# shoot1.net
KiCad netlist of a schematic drawn in Altium Designer
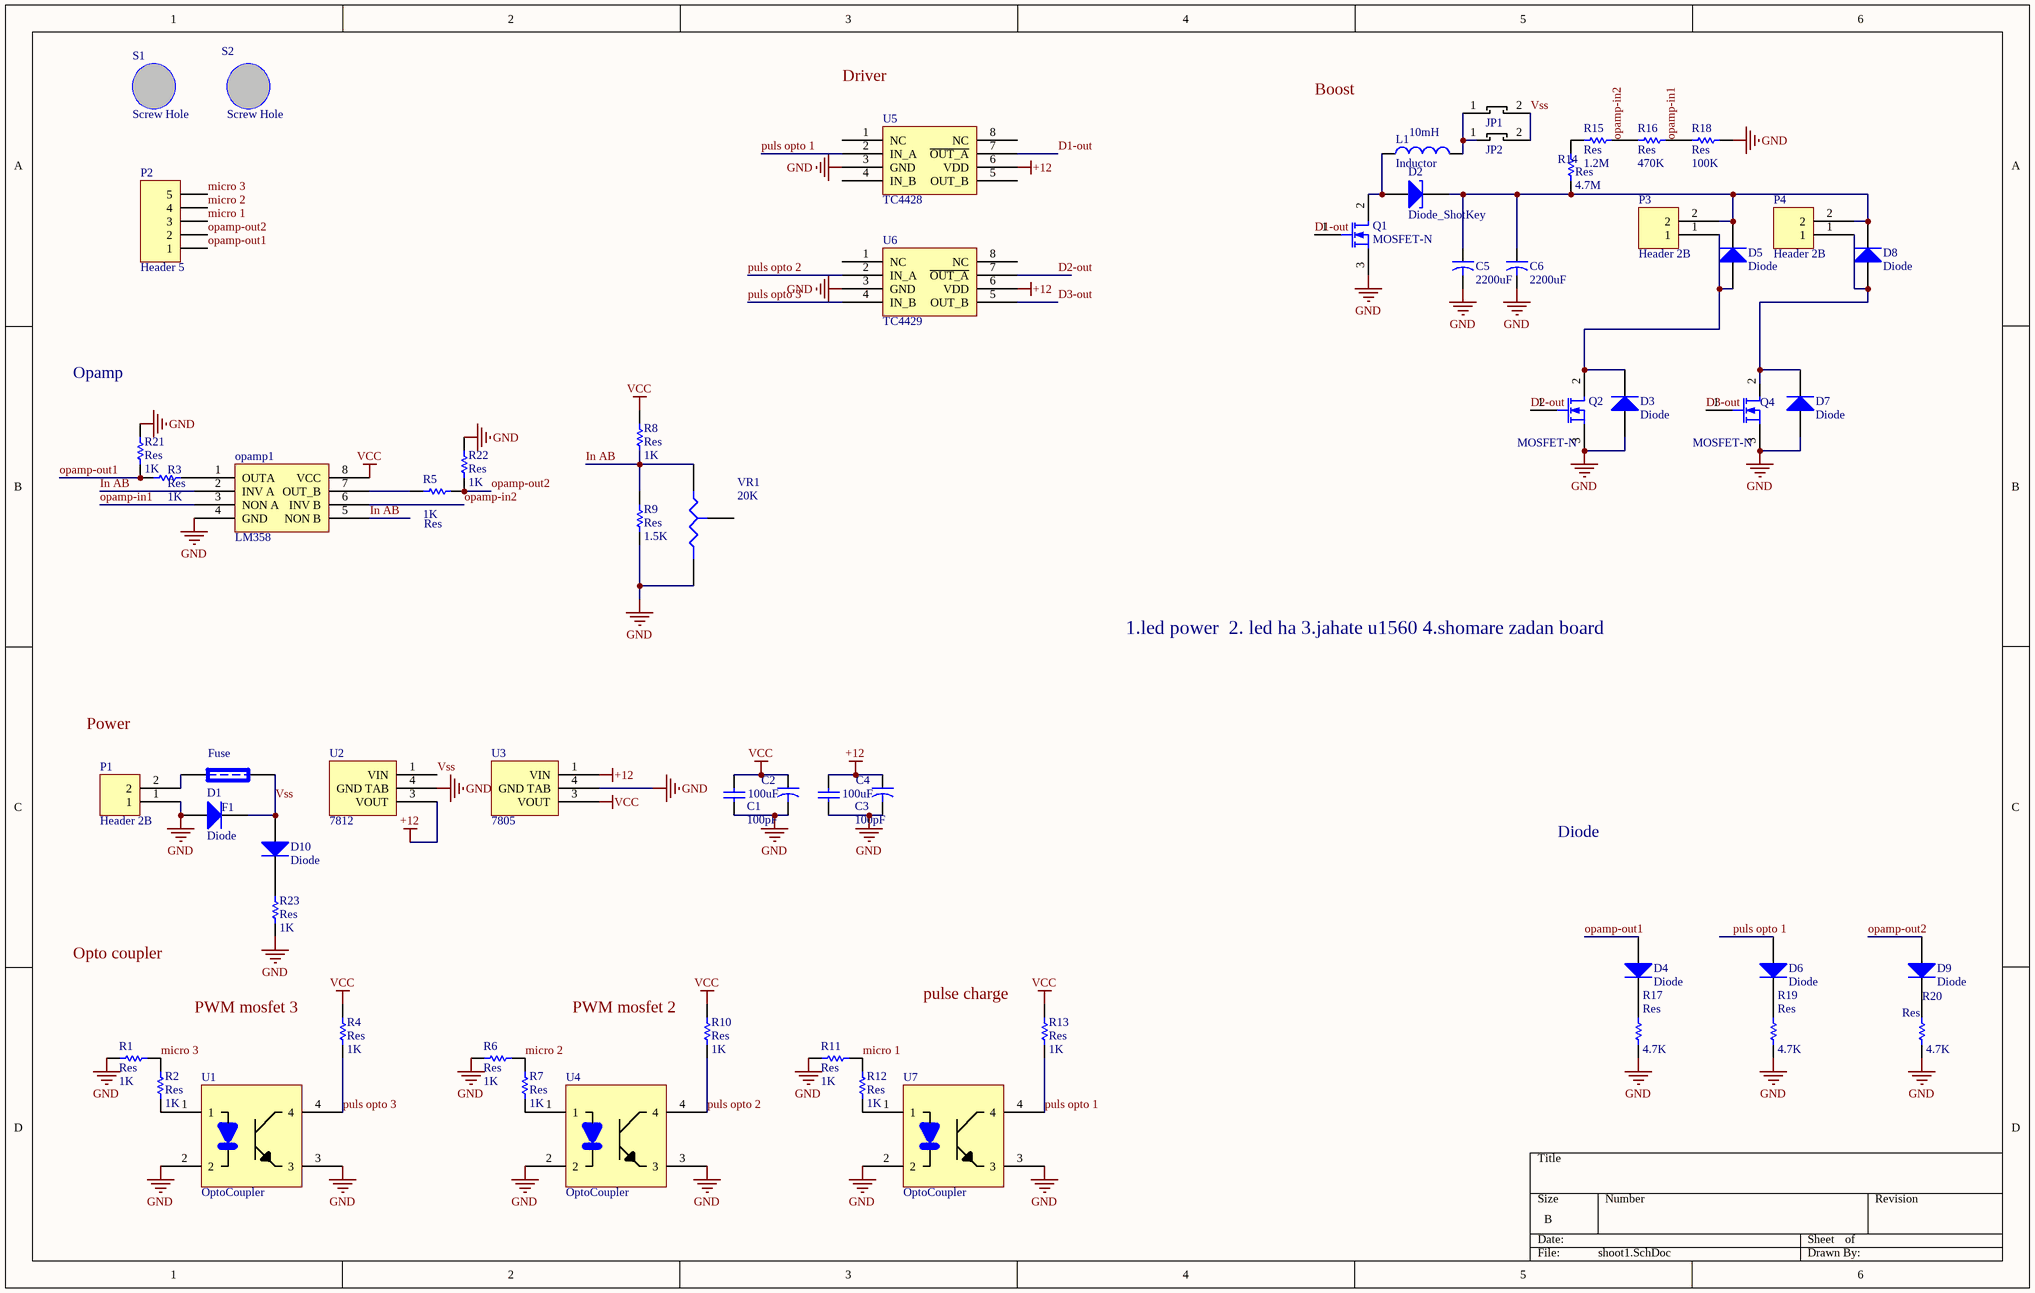
[diagram p0: shoot1.SchDoc]

(export (version "E")
  (design (tool "Eeschema 10.0.6"))
  (components
    (comp (ref "C1")
      (value "100pF")
      (footprint "2012[0805]")
      (description "Capacitor")
      (fields (field (name "Comment") "Cap_UP") (field (name "PUBLISHER") "Altium Limited"))
      (libsource (lib "KN2CLib") (part "Cap_UP"))
    )
    (comp (ref "C2")
      (value "100uF")
      (footprint "EL_M")
      (description "Capacitor")
      (fields (field (name "Comment") "Cap_El") (field (name "PUBLISHER") "Altium Limited"))
      (libsource (lib "KN2CLib") (part "Cap_El"))
    )
    (comp (ref "C3")
      (value "100pF")
      (footprint "2012[0805]")
      (description "Capacitor")
      (fields (field (name "Comment") "Cap_UP") (field (name "PUBLISHER") "Altium Limited"))
      (libsource (lib "KN2CLib") (part "Cap_UP"))
    )
    (comp (ref "C4")
      (value "100uF")
      (footprint "EL_M")
      (description "Capacitor")
      (fields (field (name "Comment") "Cap_El") (field (name "PUBLISHER") "Altium Limited"))
      (libsource (lib "KN2CLib") (part "Cap_El"))
    )
    (comp (ref "C5")
      (value "2200uF")
      (footprint "CAP")
      (description "Capacitor")
      (fields (field (name "Comment") "Cap_El_200V") (field (name "PUBLISHER") "Altium Limited"))
      (libsource (lib "KN2CLib") (part "Cap_El_200V"))
    )
    (comp (ref "C6")
      (value "2200uF")
      (footprint "CAP")
      (description "Capacitor")
      (fields (field (name "Comment") "Cap_El_200V") (field (name "PUBLISHER") "Altium Limited"))
      (libsource (lib "KN2CLib") (part "Cap_El_200V"))
    )
    (comp (ref "D1")
      (value "Diode")
      (footprint "US1M")
      (description "1 Amp General Purpose Rectifier")
      (fields (field (name "PUBLISHER") "Altium Limited"))
      (libsource (lib "KN2CLib") (part "Diode"))
    )
    (comp (ref "D2")
      (value "Diode_ShotKey")
      (footprint "TO-220A - duplicate")
      (description "1 Amp General Purpose Rectifier")
      (fields (field (name "PUBLISHER") "Altium Limited"))
      (libsource (lib "KN2CLib") (part "Diode_ShotKey"))
    )
    (comp (ref "D3")
      (value "Diode")
      (footprint "DIO10.46-5.3X2.8")
      (description "1 Amp General Purpose Rectifier")
      (fields (field (name "PUBLISHER") "Altium Limited"))
      (libsource (lib "KN2CLib") (part "Diode"))
    )
    (comp (ref "D4")
      (value "Diode")
      (footprint "2012[0805]")
      (description "1 Amp General Purpose Rectifier")
      (fields (field (name "PUBLISHER") "Altium Limited"))
      (libsource (lib "KN2CLib") (part "Diode"))
    )
    (comp (ref "D5")
      (value "Diode")
      (footprint "DIO10.46-5.3X2.8")
      (description "1 Amp General Purpose Rectifier")
      (fields (field (name "PUBLISHER") "Altium Limited"))
      (libsource (lib "KN2CLib") (part "Diode"))
    )
    (comp (ref "D6")
      (value "Diode")
      (footprint "2012[0805]")
      (description "1 Amp General Purpose Rectifier")
      (fields (field (name "PUBLISHER") "Altium Limited"))
      (libsource (lib "KN2CLib") (part "Diode"))
    )
    (comp (ref "D7")
      (value "Diode")
      (footprint "DIO10.46-5.3X2.8")
      (description "1 Amp General Purpose Rectifier")
      (fields (field (name "PUBLISHER") "Altium Limited"))
      (libsource (lib "KN2CLib") (part "Diode"))
    )
    (comp (ref "D8")
      (value "Diode")
      (footprint "DIO10.46-5.3X2.8")
      (description "1 Amp General Purpose Rectifier")
      (fields (field (name "PUBLISHER") "Altium Limited"))
      (libsource (lib "KN2CLib") (part "Diode"))
    )
    (comp (ref "D9")
      (value "Diode")
      (footprint "2012[0805]")
      (description "1 Amp General Purpose Rectifier")
      (fields (field (name "PUBLISHER") "Altium Limited"))
      (libsource (lib "KN2CLib") (part "Diode"))
    )
    (comp (ref "D10")
      (value "Diode")
      (footprint "2012[0805]")
      (description "1 Amp General Purpose Rectifier")
      (fields (field (name "PUBLISHER") "Altium Limited"))
      (libsource (lib "KN2CLib") (part "Diode"))
    )
    (comp (ref "F1")
      (value "Fuse")
      (footprint "fuse new")
      (fields (field (name "PUBLISHER") "Altium Limited"))
      (libsource (lib "KN2CLib") (part "Fuse"))
    )
    (comp (ref "JP1") (value "JUMPER") (footprint "JPR") (libsource (lib "KN2CLib") (part "JUMPER")))
    (comp (ref "JP2") (value "JUMPER") (footprint "JPR") (libsource (lib "KN2CLib") (part "JUMPER")))
    (comp (ref "L1")
      (value "Inductor")
      (footprint "Mh2")
      (fields (field (name "ALTIUM_VALUE") "10mH") (field (name "PUBLISHER") "Altium Limited"))
      (libsource (lib "KN2CLib") (part "Inductor"))
    )
    (comp (ref "opamp1")
      (value "LM358")
      (footprint "8 pin SOIC_N")
      (description "Dual MOSFET Driver")
      (libsource (lib "KN2CLib") (part "7667"))
    )
    (comp (ref "P1") (value "Header 2B") (footprint "BHDR1X2") (libsource (lib "KN2CLib") (part "Header 2B")))
    (comp (ref "P2")
      (value "Header 5")
      (footprint "SHEADER 5")
      (description "Header, 5-Pin")
      (fields (field (name "PUBLISHER") "Altium Limited"))
      (libsource (lib "KN2CLib") (part "Header 5"))
    )
    (comp (ref "P3") (value "Header 2B") (footprint "BHDR1X2") (libsource (lib "KN2CLib") (part "Header 2B")))
    (comp (ref "P4") (value "Header 2B") (footprint "BHDR1X2") (libsource (lib "KN2CLib") (part "Header 2B")))
    (comp (ref "Q1")
      (value "MOSFET-N")
      (footprint "TO247")
      (description "N-Channel MOSFET")
      (fields (field (name "PUBLISHER") "Altium Limited"))
      (libsource (lib "KN2CLib") (part "MOSFET-N"))
    )
    (comp (ref "Q2")
      (value "MOSFET-N")
      (footprint "TO247")
      (description "N-Channel MOSFET")
      (fields (field (name "PUBLISHER") "Altium Limited"))
      (libsource (lib "KN2CLib") (part "MOSFET-N"))
    )
    (comp (ref "Q4")
      (value "MOSFET-N")
      (footprint "TO247")
      (description "N-Channel MOSFET")
      (fields (field (name "PUBLISHER") "Altium Limited"))
      (libsource (lib "KN2CLib") (part "MOSFET-N"))
    )
    (comp (ref "R1")
      (value "Res")
      (footprint "2012[0805]")
      (description "Semiconductor Resistor")
      (fields (field (name "ALTIUM_VALUE") "1K") (field (name "PUBLISHER") "Altium Limited"))
      (libsource (lib "KN2CLib") (part "Res"))
    )
    (comp (ref "R2")
      (value "Res")
      (footprint "2012[0805]")
      (description "Semiconductor Resistor")
      (fields (field (name "ALTIUM_VALUE") "1K") (field (name "PUBLISHER") "Altium Limited"))
      (libsource (lib "KN2CLib") (part "Res"))
    )
    (comp (ref "R3")
      (value "Res")
      (footprint "2012[0805]")
      (description "Semiconductor Resistor")
      (fields (field (name "ALTIUM_VALUE") "1K") (field (name "PUBLISHER") "Altium Limited"))
      (libsource (lib "KN2CLib") (part "Res"))
    )
    (comp (ref "R4")
      (value "Res")
      (footprint "2012[0805]")
      (description "Semiconductor Resistor")
      (fields (field (name "ALTIUM_VALUE") "1K") (field (name "PUBLISHER") "Altium Limited"))
      (libsource (lib "KN2CLib") (part "Res"))
    )
    (comp (ref "R5")
      (value "Res")
      (footprint "2012[0805]")
      (description "Semiconductor Resistor")
      (fields (field (name "ALTIUM_VALUE") "1K") (field (name "PUBLISHER") "Altium Limited"))
      (libsource (lib "KN2CLib") (part "Res"))
    )
    (comp (ref "R6")
      (value "Res")
      (footprint "2012[0805]")
      (description "Semiconductor Resistor")
      (fields (field (name "ALTIUM_VALUE") "1K") (field (name "PUBLISHER") "Altium Limited"))
      (libsource (lib "KN2CLib") (part "Res"))
    )
    (comp (ref "R7")
      (value "Res")
      (footprint "2012[0805]")
      (description "Semiconductor Resistor")
      (fields (field (name "ALTIUM_VALUE") "1K") (field (name "PUBLISHER") "Altium Limited"))
      (libsource (lib "KN2CLib") (part "Res"))
    )
    (comp (ref "R8")
      (value "Res")
      (footprint "2012[0805]")
      (description "Semiconductor Resistor")
      (fields (field (name "ALTIUM_VALUE") "1K") (field (name "PUBLISHER") "Altium Limited"))
      (libsource (lib "KN2CLib") (part "Res"))
    )
    (comp (ref "R9")
      (value "Res")
      (footprint "2012[0805]")
      (description "Semiconductor Resistor")
      (fields (field (name "ALTIUM_VALUE") "1.5K") (field (name "PUBLISHER") "Altium Limited"))
      (libsource (lib "KN2CLib") (part "Res"))
    )
    (comp (ref "R10")
      (value "Res")
      (footprint "2012[0805]")
      (description "Semiconductor Resistor")
      (fields (field (name "ALTIUM_VALUE") "1K") (field (name "PUBLISHER") "Altium Limited"))
      (libsource (lib "KN2CLib") (part "Res"))
    )
    (comp (ref "R11")
      (value "Res")
      (footprint "2012[0805]")
      (description "Semiconductor Resistor")
      (fields (field (name "ALTIUM_VALUE") "1K") (field (name "PUBLISHER") "Altium Limited"))
      (libsource (lib "KN2CLib") (part "Res"))
    )
    (comp (ref "R12")
      (value "Res")
      (footprint "2012[0805]")
      (description "Semiconductor Resistor")
      (fields (field (name "ALTIUM_VALUE") "1K") (field (name "PUBLISHER") "Altium Limited"))
      (libsource (lib "KN2CLib") (part "Res"))
    )
    (comp (ref "R13")
      (value "Res")
      (footprint "2012[0805]")
      (description "Semiconductor Resistor")
      (fields (field (name "ALTIUM_VALUE") "1K") (field (name "PUBLISHER") "Altium Limited"))
      (libsource (lib "KN2CLib") (part "Res"))
    )
    (comp (ref "R14")
      (value "Res")
      (footprint "2012[0805]")
      (description "Semiconductor Resistor")
      (fields (field (name "ALTIUM_VALUE") "4.7M") (field (name "PUBLISHER") "Altium Limited"))
      (libsource (lib "KN2CLib") (part "Res"))
    )
    (comp (ref "R15")
      (value "Res")
      (footprint "2012[0805]")
      (description "Semiconductor Resistor")
      (fields (field (name "ALTIUM_VALUE") "1.2M") (field (name "PUBLISHER") "Altium Limited"))
      (libsource (lib "KN2CLib") (part "Res"))
    )
    (comp (ref "R16")
      (value "Res")
      (footprint "2012[0805]")
      (description "Semiconductor Resistor")
      (fields (field (name "ALTIUM_VALUE") "470K") (field (name "PUBLISHER") "Altium Limited"))
      (libsource (lib "KN2CLib") (part "Res"))
    )
    (comp (ref "R17")
      (value "Res")
      (footprint "2012[0805]")
      (description "Semiconductor Resistor")
      (fields (field (name "ALTIUM_VALUE") "4.7K") (field (name "PUBLISHER") "Altium Limited"))
      (libsource (lib "KN2CLib") (part "Res"))
    )
    (comp (ref "R18")
      (value "Res")
      (footprint "2012[0805]")
      (description "Semiconductor Resistor")
      (fields (field (name "ALTIUM_VALUE") "100K") (field (name "PUBLISHER") "Altium Limited"))
      (libsource (lib "KN2CLib") (part "Res"))
    )
    (comp (ref "R19")
      (value "Res")
      (footprint "2012[0805]")
      (description "Semiconductor Resistor")
      (fields (field (name "ALTIUM_VALUE") "4.7K") (field (name "PUBLISHER") "Altium Limited"))
      (libsource (lib "KN2CLib") (part "Res"))
    )
    (comp (ref "R20")
      (value "Res")
      (footprint "2012[0805]")
      (description "Semiconductor Resistor")
      (fields (field (name "ALTIUM_VALUE") "4.7K") (field (name "PUBLISHER") "Altium Limited"))
      (libsource (lib "KN2CLib") (part "Res"))
    )
    (comp (ref "R21")
      (value "Res")
      (footprint "2012[0805]")
      (description "Semiconductor Resistor")
      (fields (field (name "ALTIUM_VALUE") "1K") (field (name "PUBLISHER") "Altium Limited"))
      (libsource (lib "KN2CLib") (part "Res"))
    )
    (comp (ref "R22")
      (value "Res")
      (footprint "2012[0805]")
      (description "Semiconductor Resistor")
      (fields (field (name "ALTIUM_VALUE") "1K") (field (name "PUBLISHER") "Altium Limited"))
      (libsource (lib "KN2CLib") (part "Res"))
    )
    (comp (ref "R23")
      (value "Res")
      (footprint "2012[0805]")
      (description "Semiconductor Resistor")
      (fields (field (name "ALTIUM_VALUE") "1K") (field (name "PUBLISHER") "Altium Limited"))
      (libsource (lib "KN2CLib") (part "Res"))
    )
    (comp (ref "S1")
      (value "Screw Hole")
      (footprint "Screw Holw 3-6 mm")
      (libsource (lib "KN2CLib") (part "Screw Hole"))
    )
    (comp (ref "S2")
      (value "Screw Hole")
      (footprint "Screw Holw 3-6 mm")
      (libsource (lib "KN2CLib") (part "Screw Hole"))
    )
    (comp (ref "U1") (value "OptoCoupler") (footprint "opto_smd") (libsource (lib "KN2CLib") (part "TLP521")))
    (comp (ref "U2") (value "7812") (footprint "D-PACK") (libsource (lib "KN2CLib") (part "7812")))
    (comp (ref "U3") (value "7805") (footprint "D-PACK") (libsource (lib "KN2CLib") (part "7805")))
    (comp (ref "U4") (value "OptoCoupler") (footprint "opto_smd") (libsource (lib "KN2CLib") (part "TLP521")))
    (comp (ref "U5")
      (value "TC4428")
      (footprint "SO-8_M")
      (description "Dual MOSFET Driver")
      (libsource (lib "KN2CLib") (part "TC4428"))
    )
    (comp (ref "U6")
      (value "TC4429")
      (footprint "SO-8_M")
      (description "Dual MOSFET Driver")
      (libsource (lib "KN2CLib") (part "TC4428"))
    )
    (comp (ref "U7") (value "OptoCoupler") (footprint "opto_smd") (libsource (lib "KN2CLib") (part "TLP521")))
    (comp (ref "VR1")
      (value "20K")
      (footprint "MULTITURN")
      (description "Tapped Resistor")
      (fields (field (name "Comment") "Res Tap") (field (name "PUBLISHER") "Altium Limited"))
      (libsource (lib "KN2CLib") (part "Res Tap"))
    )
  )
  (nets
    (net (code "1") (name "+12") (class "Default")
      (node (ref "C3") (pin "2") (pinfunction "2_2") (pintype "passive"))
      (node (ref "C4") (pin "1") (pinfunction "1_1") (pintype "passive"))
      (node (ref "U2") (pin "3") (pinfunction "VOUT_3") (pintype "passive"))
      (node (ref "U3") (pin "1") (pinfunction "VIN_1") (pintype "passive"))
      (node (ref "U5") (pin "6") (pinfunction "VDD_6") (pintype "passive"))
      (node (ref "U6") (pin "6") (pinfunction "VDD_6") (pintype "passive"))
    )
    (net (code "3") (name "/D1-out") (class "Default")
      (node (ref "Q1") (pin "1") (pinfunction "G_1") (pintype "passive"))
      (node (ref "U5") (pin "7") (pinfunction "~{OUT_A}_7") (pintype "passive"))
    )
    (net (code "4") (name "/D2-out") (class "Default")
      (node (ref "Q2") (pin "1") (pinfunction "G_1") (pintype "passive"))
      (node (ref "U6") (pin "7") (pinfunction "~{OUT_A}_7") (pintype "passive"))
    )
    (net (code "5") (name "/D3-out") (class "Default")
      (node (ref "Q4") (pin "1") (pinfunction "G_1") (pintype "passive"))
      (node (ref "U6") (pin "5") (pinfunction "OUT_B_5") (pintype "passive"))
    )
    (net (code "7") (name "/In AB") (class "Default")
      (node (ref "R8") (pin "1") (pinfunction "1_1") (pintype "passive"))
      (node (ref "R9") (pin "2") (pinfunction "2_2") (pintype "passive"))
      (node (ref "VR1") (pin "1") (pinfunction "A_1") (pintype "passive"))
      (node (ref "opamp1") (pin "2") (pinfunction "INV_A_2") (pintype "passive"))
      (node (ref "opamp1") (pin "5") (pinfunction "NON_B_5") (pintype "passive"))
    )
    (net (code "12") (name "/Vss") (class "Default")
      (node (ref "D1") (pin "2") (pinfunction "K_2") (pintype "passive"))
      (node (ref "D10") (pin "1") (pinfunction "A_1") (pintype "passive"))
      (node (ref "F1") (pin "2") (pinfunction "2_2") (pintype "passive"))
      (node (ref "JP1") (pin "2") (pinfunction "2_2") (pintype "passive"))
      (node (ref "JP2") (pin "2") (pinfunction "2_2") (pintype "passive"))
      (node (ref "U2") (pin "1") (pinfunction "VIN_1") (pintype "passive"))
    )
    (net (code "13") (name "/micro 1") (class "Default")
      (node (ref "P2") (pin "3") (pinfunction "3_3") (pintype "passive"))
      (node (ref "R11") (pin "1") (pinfunction "1_1") (pintype "passive"))
      (node (ref "R12") (pin "2") (pinfunction "2_2") (pintype "passive"))
    )
    (net (code "14") (name "/micro 2") (class "Default")
      (node (ref "P2") (pin "4") (pinfunction "4_4") (pintype "passive"))
      (node (ref "R6") (pin "1") (pinfunction "1_1") (pintype "passive"))
      (node (ref "R7") (pin "2") (pinfunction "2_2") (pintype "passive"))
    )
    (net (code "15") (name "/micro 3") (class "Default")
      (node (ref "P2") (pin "5") (pinfunction "5_5") (pintype "passive"))
      (node (ref "R1") (pin "1") (pinfunction "1_1") (pintype "passive"))
      (node (ref "R2") (pin "2") (pinfunction "2_2") (pintype "passive"))
    )
    (net (code "16") (name "/opamp-in1") (class "Default")
      (node (ref "R16") (pin "1") (pinfunction "1_1") (pintype "passive"))
      (node (ref "R18") (pin "2") (pinfunction "2_2") (pintype "passive"))
      (node (ref "opamp1") (pin "3") (pinfunction "NON_A_3") (pintype "passive"))
    )
    (net (code "17") (name "/opamp-in2") (class "Default")
      (node (ref "R15") (pin "1") (pinfunction "1_1") (pintype "passive"))
      (node (ref "R16") (pin "2") (pinfunction "2_2") (pintype "passive"))
      (node (ref "opamp1") (pin "6") (pinfunction "INV_B_6") (pintype "passive"))
    )
    (net (code "18") (name "/opamp-out1") (class "Default")
      (node (ref "D4") (pin "1") (pinfunction "A_1") (pintype "passive"))
      (node (ref "P2") (pin "1") (pinfunction "1_1") (pintype "passive"))
      (node (ref "R21") (pin "1") (pinfunction "1_1") (pintype "passive"))
      (node (ref "R3") (pin "2") (pinfunction "2_2") (pintype "passive"))
    )
    (net (code "19") (name "/opamp-out2") (class "Default")
      (node (ref "D9") (pin "1") (pinfunction "A_1") (pintype "passive"))
      (node (ref "P2") (pin "2") (pinfunction "2_2") (pintype "passive"))
      (node (ref "R22") (pin "1") (pinfunction "1_1") (pintype "passive"))
      (node (ref "R5") (pin "1") (pinfunction "1_1") (pintype "passive"))
    )
    (net (code "20") (name "/puls opto 1") (class "Default")
      (node (ref "D6") (pin "1") (pinfunction "A_1") (pintype "passive"))
      (node (ref "R13") (pin "1") (pinfunction "1_1") (pintype "passive"))
      (node (ref "U5") (pin "2") (pinfunction "IN_A_2") (pintype "passive"))
      (node (ref "U7") (pin "4") (pinfunction "4_4") (pintype "passive"))
    )
    (net (code "21") (name "/puls opto 2") (class "Default")
      (node (ref "R10") (pin "1") (pinfunction "1_1") (pintype "passive"))
      (node (ref "U4") (pin "4") (pinfunction "4_4") (pintype "passive"))
      (node (ref "U6") (pin "2") (pinfunction "IN_A_2") (pintype "passive"))
    )
    (net (code "22") (name "/puls opto 3") (class "Default")
      (node (ref "R4") (pin "1") (pinfunction "1_1") (pintype "passive"))
      (node (ref "U1") (pin "4") (pinfunction "4_4") (pintype "passive"))
      (node (ref "U6") (pin "4") (pinfunction "IN_B_4") (pintype "passive"))
    )
    (net (code "24") (name "GND") (class "Default")
      (node (ref "C1") (pin "1") (pinfunction "1_1") (pintype "passive"))
      (node (ref "C2") (pin "2") (pinfunction "2_2") (pintype "passive"))
      (node (ref "C3") (pin "1") (pinfunction "1_1") (pintype "passive"))
      (node (ref "C4") (pin "2") (pinfunction "2_2") (pintype "passive"))
      (node (ref "C5") (pin "2") (pinfunction "2_2") (pintype "passive"))
      (node (ref "C6") (pin "2") (pinfunction "2_2") (pintype "passive"))
      (node (ref "D1") (pin "1") (pinfunction "A_1") (pintype "passive"))
      (node (ref "D3") (pin "1") (pinfunction "A_1") (pintype "passive"))
      (node (ref "D7") (pin "1") (pinfunction "A_1") (pintype "passive"))
      (node (ref "P1") (pin "1") (pinfunction "1_1") (pintype "passive"))
      (node (ref "Q1") (pin "3") (pinfunction "S_3") (pintype "passive"))
      (node (ref "Q2") (pin "3") (pinfunction "S_3") (pintype "passive"))
      (node (ref "Q4") (pin "3") (pinfunction "S_3") (pintype "passive"))
      (node (ref "R1") (pin "2") (pinfunction "2_2") (pintype "passive"))
      (node (ref "R11") (pin "2") (pinfunction "2_2") (pintype "passive"))
      (node (ref "R17") (pin "1") (pinfunction "1_1") (pintype "passive"))
      (node (ref "R18") (pin "1") (pinfunction "1_1") (pintype "passive"))
      (node (ref "R19") (pin "1") (pinfunction "1_1") (pintype "passive"))
      (node (ref "R20") (pin "1") (pinfunction "1_1") (pintype "passive"))
      (node (ref "R21") (pin "2") (pinfunction "2_2") (pintype "passive"))
      (node (ref "R22") (pin "2") (pinfunction "2_2") (pintype "passive"))
      (node (ref "R23") (pin "1") (pinfunction "1_1") (pintype "passive"))
      (node (ref "R6") (pin "2") (pinfunction "2_2") (pintype "passive"))
      (node (ref "R9") (pin "1") (pinfunction "1_1") (pintype "passive"))
      (node (ref "U1") (pin "2") (pinfunction "2_2") (pintype "passive"))
      (node (ref "U1") (pin "3") (pinfunction "3_3") (pintype "passive"))
      (node (ref "U2") (pin "4") (pinfunction "GND_TAB_4") (pintype "passive"))
      (node (ref "U3") (pin "4") (pinfunction "GND_TAB_4") (pintype "passive"))
      (node (ref "U4") (pin "2") (pinfunction "2_2") (pintype "passive"))
      (node (ref "U4") (pin "3") (pinfunction "3_3") (pintype "passive"))
      (node (ref "U5") (pin "3") (pinfunction "GND_3") (pintype "passive"))
      (node (ref "U6") (pin "3") (pinfunction "GND_3") (pintype "passive"))
      (node (ref "U7") (pin "2") (pinfunction "2_2") (pintype "passive"))
      (node (ref "U7") (pin "3") (pinfunction "3_3") (pintype "passive"))
      (node (ref "VR1") (pin "2") (pinfunction "B_2") (pintype "passive"))
      (node (ref "opamp1") (pin "4") (pinfunction "GND_4") (pintype "passive"))
    )
    (net (code "25") (name "Net-(D2-A)") (class "Default")
      (node (ref "D2") (pin "2") (pinfunction "A_2") (pintype "passive"))
      (node (ref "L1") (pin "1") (pinfunction "1_1") (pintype "passive"))
      (node (ref "Q1") (pin "2") (pinfunction "D_2") (pintype "passive"))
    )
    (net (code "26") (name "Net-(D2-K)") (class "Default")
      (node (ref "C5") (pin "1") (pinfunction "1_1") (pintype "passive"))
      (node (ref "C6") (pin "1") (pinfunction "1_1") (pintype "passive"))
      (node (ref "D2") (pin "1") (pinfunction "K_1") (pintype "passive"))
      (node (ref "D5") (pin "2") (pinfunction "K_2") (pintype "passive"))
      (node (ref "D8") (pin "2") (pinfunction "K_2") (pintype "passive"))
      (node (ref "P3") (pin "2") (pinfunction "2_2") (pintype "passive"))
      (node (ref "P4") (pin "2") (pinfunction "2_2") (pintype "passive"))
      (node (ref "R14") (pin "1") (pinfunction "1_1") (pintype "passive"))
    )
    (net (code "27") (name "Net-(D3-K)") (class "Default")
      (node (ref "D3") (pin "2") (pinfunction "K_2") (pintype "passive"))
      (node (ref "D5") (pin "1") (pinfunction "A_1") (pintype "passive"))
      (node (ref "P3") (pin "1") (pinfunction "1_1") (pintype "passive"))
      (node (ref "Q2") (pin "2") (pinfunction "D_2") (pintype "passive"))
    )
    (net (code "28") (name "Net-(D4-K)") (class "Default")
      (node (ref "D4") (pin "2") (pinfunction "K_2") (pintype "passive"))
      (node (ref "R17") (pin "2") (pinfunction "2_2") (pintype "passive"))
    )
    (net (code "29") (name "Net-(D6-K)") (class "Default")
      (node (ref "D6") (pin "2") (pinfunction "K_2") (pintype "passive"))
      (node (ref "R19") (pin "2") (pinfunction "2_2") (pintype "passive"))
    )
    (net (code "30") (name "Net-(D7-K)") (class "Default")
      (node (ref "D7") (pin "2") (pinfunction "K_2") (pintype "passive"))
      (node (ref "D8") (pin "1") (pinfunction "A_1") (pintype "passive"))
      (node (ref "P4") (pin "1") (pinfunction "1_1") (pintype "passive"))
      (node (ref "Q4") (pin "2") (pinfunction "D_2") (pintype "passive"))
    )
    (net (code "31") (name "Net-(D9-K)") (class "Default")
      (node (ref "D9") (pin "2") (pinfunction "K_2") (pintype "passive"))
      (node (ref "R20") (pin "2") (pinfunction "2_2") (pintype "passive"))
    )
    (net (code "32") (name "Net-(D10-K)") (class "Default")
      (node (ref "D10") (pin "2") (pinfunction "K_2") (pintype "passive"))
      (node (ref "R23") (pin "2") (pinfunction "2_2") (pintype "passive"))
    )
    (net (code "33") (name "Net-(F1-Pad1)") (class "Default")
      (node (ref "F1") (pin "1") (pinfunction "1_1") (pintype "passive"))
      (node (ref "P1") (pin "2") (pinfunction "2_2") (pintype "passive"))
    )
    (net (code "34") (name "Net-(JP1-Pad1)") (class "Default")
      (node (ref "JP1") (pin "1") (pinfunction "1_1") (pintype "passive"))
      (node (ref "JP2") (pin "1") (pinfunction "1_1") (pintype "passive"))
      (node (ref "L1") (pin "2") (pinfunction "2_2") (pintype "passive"))
    )
    (net (code "35") (name "Net-(R2-Pad1)") (class "Default")
      (node (ref "R2") (pin "1") (pinfunction "1_1") (pintype "passive"))
      (node (ref "U1") (pin "1") (pinfunction "1_1") (pintype "passive"))
    )
    (net (code "36") (name "Net-(R7-Pad1)") (class "Default")
      (node (ref "R7") (pin "1") (pinfunction "1_1") (pintype "passive"))
      (node (ref "U4") (pin "1") (pinfunction "1_1") (pintype "passive"))
    )
    (net (code "37") (name "Net-(R12-Pad1)") (class "Default")
      (node (ref "R12") (pin "1") (pinfunction "1_1") (pintype "passive"))
      (node (ref "U7") (pin "1") (pinfunction "1_1") (pintype "passive"))
    )
    (net (code "38") (name "Net-(R14-Pad2)") (class "Default")
      (node (ref "R14") (pin "2") (pinfunction "2_2") (pintype "passive"))
      (node (ref "R15") (pin "2") (pinfunction "2_2") (pintype "passive"))
    )
    (net (code "39") (name "Net-(opamp1-OUTA)") (class "Default")
      (node (ref "R3") (pin "1") (pinfunction "1_1") (pintype "passive"))
      (node (ref "opamp1") (pin "1") (pinfunction "OUTA_1") (pintype "passive"))
    )
    (net (code "40") (name "Net-(opamp1-OUT_B)") (class "Default")
      (node (ref "R5") (pin "2") (pinfunction "2_2") (pintype "passive"))
      (node (ref "opamp1") (pin "7") (pinfunction "OUT_B_7") (pintype "passive"))
    )
    (net (code "41") (name "VCC") (class "Default")
      (node (ref "C1") (pin "2") (pinfunction "2_2") (pintype "passive"))
      (node (ref "C2") (pin "1") (pinfunction "1_1") (pintype "passive"))
      (node (ref "R10") (pin "2") (pinfunction "2_2") (pintype "passive"))
      (node (ref "R13") (pin "2") (pinfunction "2_2") (pintype "passive"))
      (node (ref "R4") (pin "2") (pinfunction "2_2") (pintype "passive"))
      (node (ref "R8") (pin "2") (pinfunction "2_2") (pintype "passive"))
      (node (ref "U3") (pin "3") (pinfunction "VOUT_3") (pintype "passive"))
      (node (ref "opamp1") (pin "8") (pinfunction "VCC_8") (pintype "passive"))
    )
    (net (code "42") (name "unconnected-(U5-IN_B-Pad4)") (class "Default")
      (node (ref "U5") (pin "4") (pinfunction "IN_B_4") (pintype "passive"))
    )
    (net (code "43") (name "unconnected-(U5-NC-Pad1)") (class "Default")
      (node (ref "U5") (pin "1") (pinfunction "NC_1") (pintype "passive"))
    )
    (net (code "44") (name "unconnected-(U5-NC-Pad8)") (class "Default")
      (node (ref "U5") (pin "8") (pinfunction "NC_8") (pintype "passive"))
    )
    (net (code "45") (name "unconnected-(U5-OUT_B-Pad5)") (class "Default")
      (node (ref "U5") (pin "5") (pinfunction "OUT_B_5") (pintype "passive"))
    )
    (net (code "46") (name "unconnected-(U6-NC-Pad1)") (class "Default")
      (node (ref "U6") (pin "1") (pinfunction "NC_1") (pintype "passive"))
    )
    (net (code "47") (name "unconnected-(U6-NC-Pad8)") (class "Default")
      (node (ref "U6") (pin "8") (pinfunction "NC_8") (pintype "passive"))
    )
    (net (code "48") (name "unconnected-(VR1-TAP-Pad3)") (class "Default")
      (node (ref "VR1") (pin "3") (pinfunction "TAP_3") (pintype "passive"))
    )
  )
)
